# 6_CLOCK.net
KiCad netlist of a schematic drawn in Altium Designer
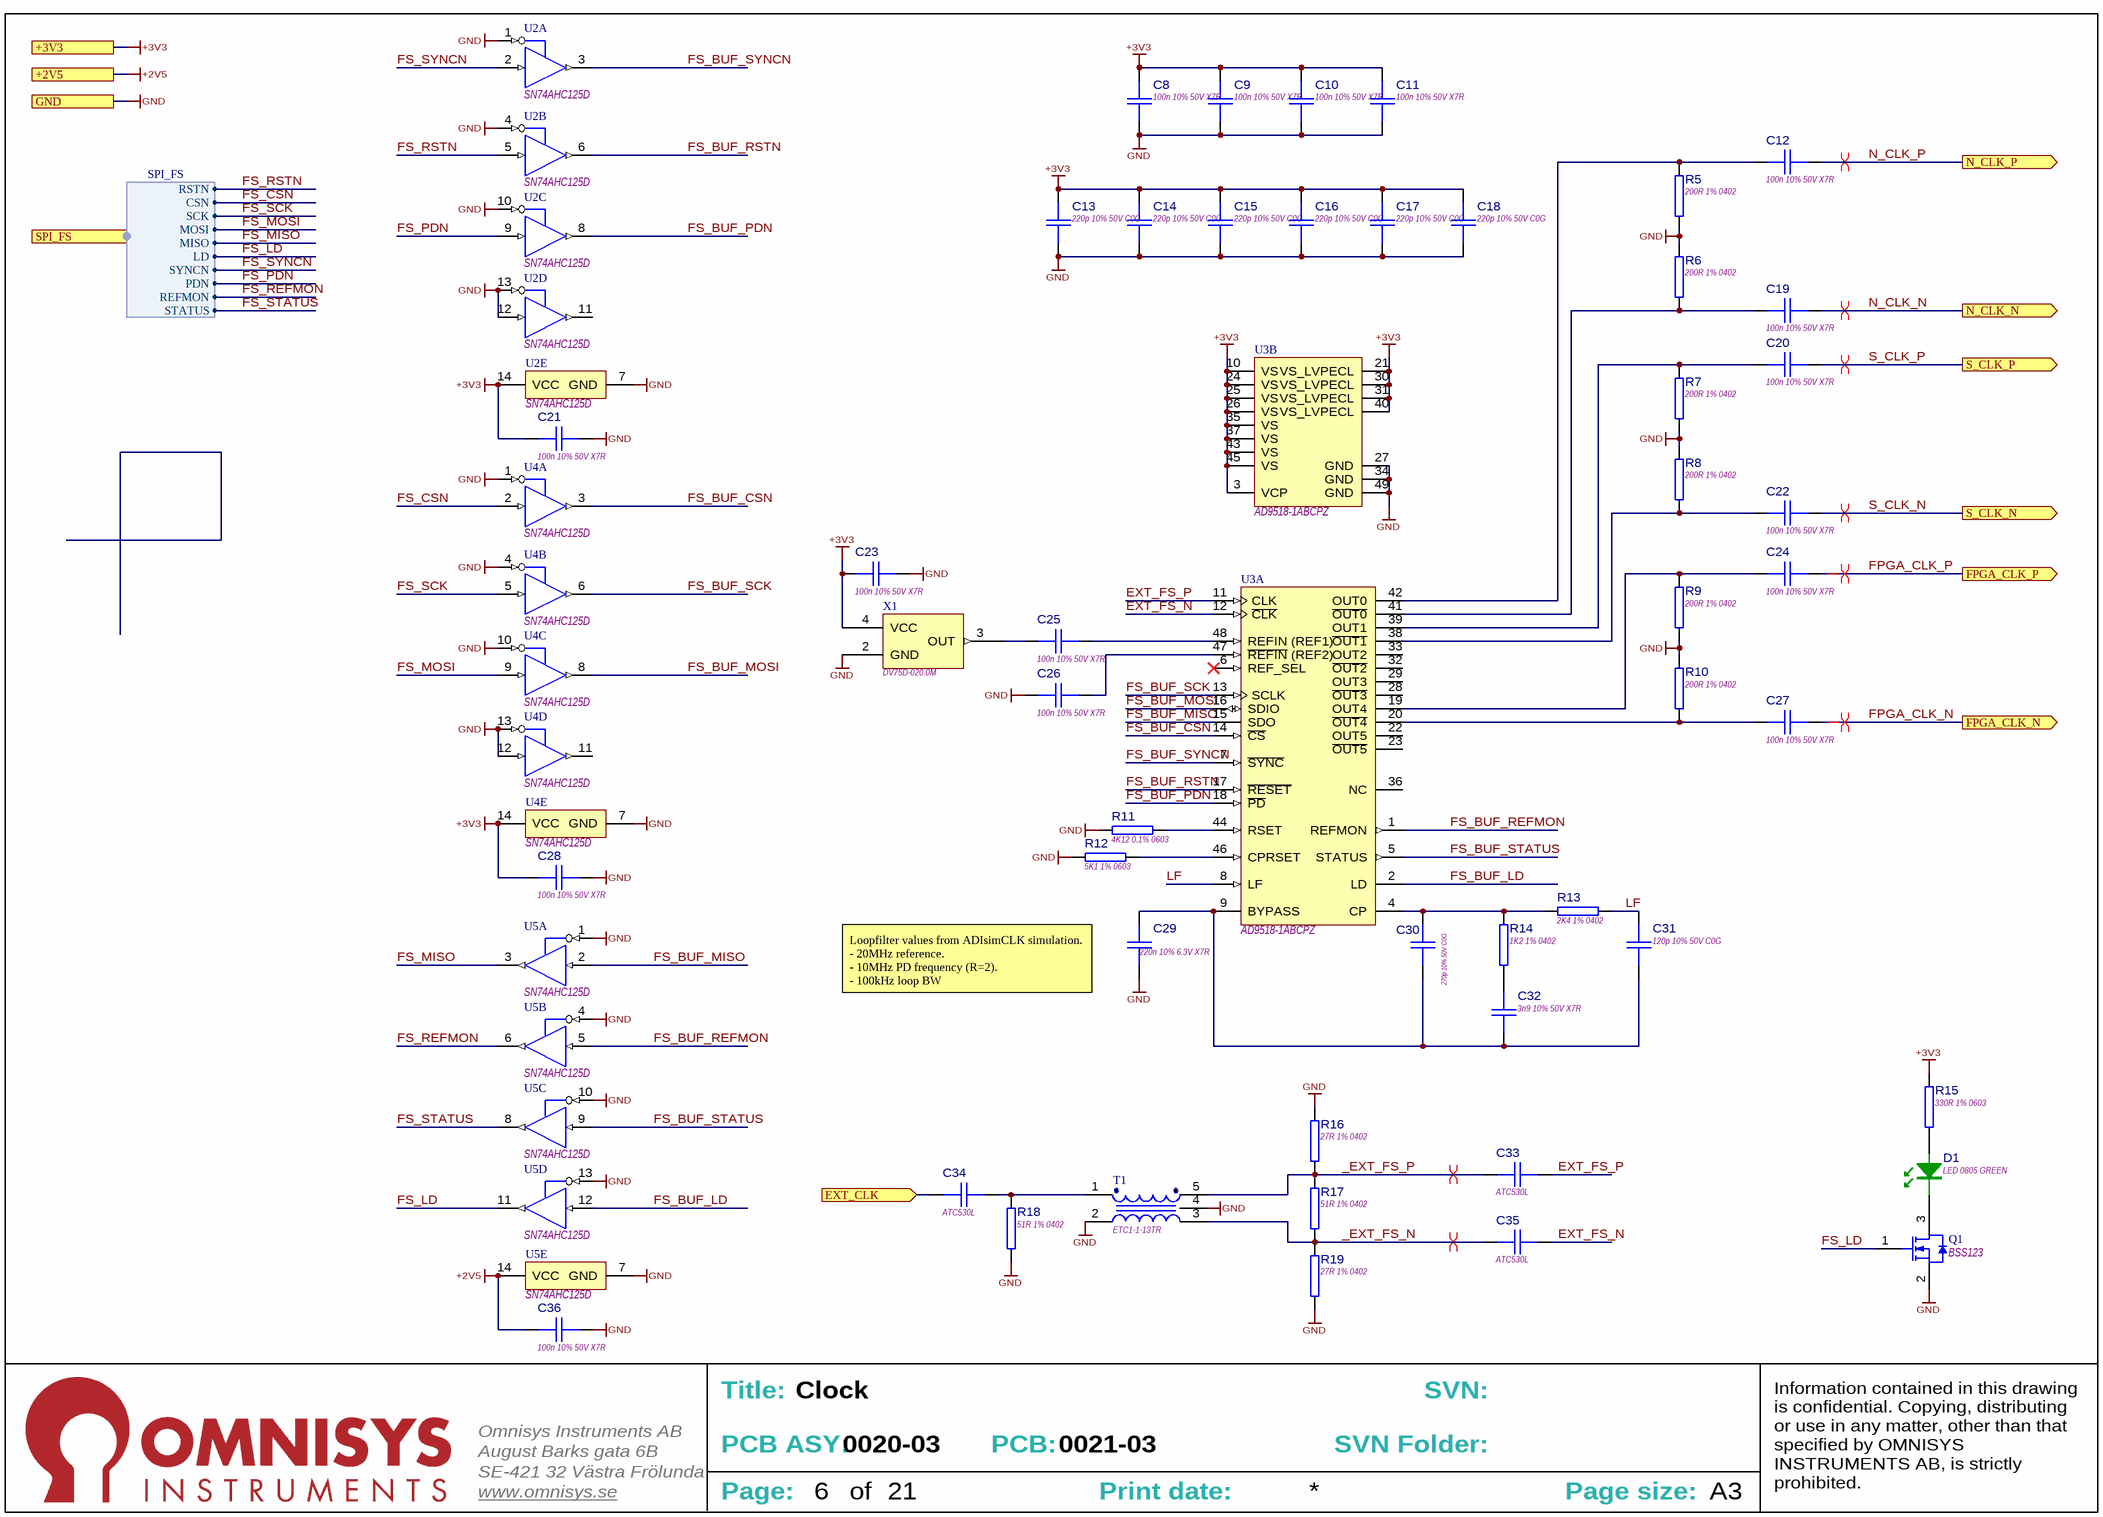
[diagram p0: [6] CLOCK.SchDoc]

(export (version "E")
  (design (tool "Eeschema 10.0.6"))
  (components
    (comp (ref "C8")
      (value "100n 10% 50V X7R")
      (footprint "CAPC1608X90N")
      (description "Ceramic Chip Capacitor, 0603/1608")
      (fields (field (name "TOLERANCE") "10%"))
      (libsource (lib "Omnisys Vault") (part "CAP-2PIN"))
    )
    (comp (ref "C9")
      (value "100n 10% 50V X7R")
      (footprint "CAPC1608X90N")
      (description "Ceramic Chip Capacitor, 0603/1608")
      (fields (field (name "TOLERANCE") "10%"))
      (libsource (lib "Omnisys Vault") (part "CAP-2PIN"))
    )
    (comp (ref "C10")
      (value "100n 10% 50V X7R")
      (footprint "CAPC1608X90N")
      (description "Ceramic Chip Capacitor, 0603/1608")
      (fields (field (name "TOLERANCE") "10%"))
      (libsource (lib "Omnisys Vault") (part "CAP-2PIN"))
    )
    (comp (ref "C11")
      (value "100n 10% 50V X7R")
      (footprint "CAPC1608X90N")
      (description "Ceramic Chip Capacitor, 0603/1608")
      (fields (field (name "TOLERANCE") "10%"))
      (libsource (lib "Omnisys Vault") (part "CAP-2PIN"))
    )
    (comp (ref "C12")
      (value "100n 10% 50V X7R")
      (footprint "CAPC1005X55L")
      (description "Ceramic Chip Capacitor, 0402/1005")
      (fields (field (name "TOLERANCE") "10%"))
      (libsource (lib "Omnisys Vault") (part "CAP-2PIN"))
    )
    (comp (ref "C13")
      (value "220p 10% 50V C0G")
      (footprint "CAPC1005X55N")
      (description "Ceramic Chip Capacitor, 0402/1005")
      (fields (field (name "TOLERANCE") "10%"))
      (libsource (lib "Omnisys Vault") (part "CAP-2PIN"))
    )
    (comp (ref "C14")
      (value "220p 10% 50V C0G")
      (footprint "CAPC1005X55N")
      (description "Ceramic Chip Capacitor, 0402/1005")
      (fields (field (name "TOLERANCE") "10%"))
      (libsource (lib "Omnisys Vault") (part "CAP-2PIN"))
    )
    (comp (ref "C15")
      (value "220p 10% 50V C0G")
      (footprint "CAPC1005X55N")
      (description "Ceramic Chip Capacitor, 0402/1005")
      (fields (field (name "TOLERANCE") "10%"))
      (libsource (lib "Omnisys Vault") (part "CAP-2PIN"))
    )
    (comp (ref "C16")
      (value "220p 10% 50V C0G")
      (footprint "CAPC1005X55N")
      (description "Ceramic Chip Capacitor, 0402/1005")
      (fields (field (name "TOLERANCE") "10%"))
      (libsource (lib "Omnisys Vault") (part "CAP-2PIN"))
    )
    (comp (ref "C17")
      (value "220p 10% 50V C0G")
      (footprint "CAPC1005X55N")
      (description "Ceramic Chip Capacitor, 0402/1005")
      (fields (field (name "TOLERANCE") "10%"))
      (libsource (lib "Omnisys Vault") (part "CAP-2PIN"))
    )
    (comp (ref "C18")
      (value "220p 10% 50V C0G")
      (footprint "CAPC1005X55N")
      (description "Ceramic Chip Capacitor, 0402/1005")
      (fields (field (name "TOLERANCE") "10%"))
      (libsource (lib "Omnisys Vault") (part "CAP-2PIN"))
    )
    (comp (ref "C19")
      (value "100n 10% 50V X7R")
      (footprint "CAPC1005X55L")
      (description "Ceramic Chip Capacitor, 0402/1005")
      (fields (field (name "TOLERANCE") "10%"))
      (libsource (lib "Omnisys Vault") (part "CAP-2PIN"))
    )
    (comp (ref "C20")
      (value "100n 10% 50V X7R")
      (footprint "CAPC1005X55L")
      (description "Ceramic Chip Capacitor, 0402/1005")
      (fields (field (name "TOLERANCE") "10%"))
      (libsource (lib "Omnisys Vault") (part "CAP-2PIN"))
    )
    (comp (ref "C21")
      (value "100n 10% 50V X7R")
      (footprint "CAPC1608X90N")
      (description "Ceramic Chip Capacitor, 0603/1608")
      (fields (field (name "TOLERANCE") "10%"))
      (libsource (lib "Omnisys Vault") (part "CAP-2PIN"))
    )
    (comp (ref "C22")
      (value "100n 10% 50V X7R")
      (footprint "CAPC1005X55L")
      (description "Ceramic Chip Capacitor, 0402/1005")
      (fields (field (name "TOLERANCE") "10%"))
      (libsource (lib "Omnisys Vault") (part "CAP-2PIN"))
    )
    (comp (ref "C23")
      (value "100n 10% 50V X7R")
      (footprint "CAPC1608X90N")
      (description "Ceramic Chip Capacitor, 0603/1608")
      (fields (field (name "TOLERANCE") "10%"))
      (libsource (lib "Omnisys Vault") (part "CAP-2PIN"))
    )
    (comp (ref "C24")
      (value "100n 10% 50V X7R")
      (footprint "CAPC1005X55L")
      (description "Ceramic Chip Capacitor, 0402/1005")
      (fields (field (name "TOLERANCE") "10%"))
      (libsource (lib "Omnisys Vault") (part "CAP-2PIN"))
    )
    (comp (ref "C25")
      (value "100n 10% 50V X7R")
      (footprint "CAPC1005X55L")
      (description "Ceramic Chip Capacitor, 0402/1005")
      (fields (field (name "TOLERANCE") "10%"))
      (libsource (lib "Omnisys Vault") (part "CAP-2PIN"))
    )
    (comp (ref "C26")
      (value "100n 10% 50V X7R")
      (footprint "CAPC1005X55L")
      (description "Ceramic Chip Capacitor, 0402/1005")
      (fields (field (name "TOLERANCE") "10%"))
      (libsource (lib "Omnisys Vault") (part "CAP-2PIN"))
    )
    (comp (ref "C27")
      (value "100n 10% 50V X7R")
      (footprint "CAPC1005X55L")
      (description "Ceramic Chip Capacitor, 0402/1005")
      (fields (field (name "TOLERANCE") "10%"))
      (libsource (lib "Omnisys Vault") (part "CAP-2PIN"))
    )
    (comp (ref "C28")
      (value "100n 10% 50V X7R")
      (footprint "CAPC1608X90N")
      (description "Ceramic Chip Capacitor, 0603/1608")
      (fields (field (name "TOLERANCE") "10%"))
      (libsource (lib "Omnisys Vault") (part "CAP-2PIN"))
    )
    (comp (ref "C29")
      (value "220n 10% 6.3V X7R")
      (footprint "CAPC1608X90L")
      (description "Ceramic Chip Capacitor, 0603/1608")
      (fields (field (name "TOLERANCE") "10%"))
      (libsource (lib "Omnisys Vault") (part "CAP-2PIN"))
    )
    (comp (ref "C30")
      (value "270p 10% 50V C0G")
      (footprint "CAPC1005X55L")
      (description "Ceramic Chip Capacitor, 0402/1005")
      (fields (field (name "TOLERANCE") "10%"))
      (libsource (lib "Omnisys Vault") (part "CAP-2PIN"))
    )
    (comp (ref "C31")
      (value "120p 10% 50V C0G")
      (footprint "CAPC1005X55L")
      (description "Ceramic Chip Capacitor, 0402/1005")
      (fields (field (name "TOLERANCE") "10%"))
      (libsource (lib "Omnisys Vault") (part "CAP-2PIN"))
    )
    (comp (ref "C32")
      (value "3n9 10% 50V X7R")
      (footprint "CAPC1005X55L")
      (description "Ceramic Chip Capacitor, 0402/1005")
      (fields (field (name "TOLERANCE") "10%"))
      (libsource (lib "Omnisys Vault") (part "CAP-2PIN"))
    )
    (comp (ref "C33")
      (value "ATC530L")
      (footprint "CAPC1005X06L")
      (description "100n 16V ±15% 0402 (1005 metric) ATC530L104KT16T")
      (fields (field (name "TOLERANCE") "±15%"))
      (libsource (lib "Omnisys Vault") (part "CAP-2PIN"))
    )
    (comp (ref "C34")
      (value "ATC530L")
      (footprint "CAPC1005X06L")
      (description "100n 16V ±15% 0402 (1005 metric) ATC530L104KT16T")
      (fields (field (name "TOLERANCE") "±15%"))
      (libsource (lib "Omnisys Vault") (part "CAP-2PIN"))
    )
    (comp (ref "C35")
      (value "ATC530L")
      (footprint "CAPC1005X06L")
      (description "100n 16V ±15% 0402 (1005 metric) ATC530L104KT16T")
      (fields (field (name "TOLERANCE") "±15%"))
      (libsource (lib "Omnisys Vault") (part "CAP-2PIN"))
    )
    (comp (ref "C36")
      (value "100n 10% 50V X7R")
      (footprint "CAPC1608X90N")
      (description "Ceramic Chip Capacitor, 0603/1608")
      (fields (field (name "TOLERANCE") "10%"))
      (libsource (lib "Omnisys Vault") (part "CAP-2PIN"))
    )
    (comp (ref "D1")
      (value "LED 0805 GREEN")
      (footprint "LED2012-GREEN")
      (libsource (lib "Omnisys Vault") (part "LED-2PIN-GREEN"))
    )
    (comp (ref "Q1")
      (value "BSS123")
      (footprint "SOT95P230X110-3N")
      (description "MOSFET N-CH 100V 170MA SOT-23")
      (fields (field (name "VOLTAGE") "100V"))
      (libsource (lib "Omnisys Vault") (part "NEMOS-GSD-3"))
    )
    (comp (ref "R5")
      (value "200R 1% 0402")
      (footprint "RESC1005L")
      (description "Thick film Chip Resistor, 0402/1005")
      (fields (field (name "POWER") "100mW") (field (name "TOLERANCE") "1%"))
      (libsource (lib "Omnisys Vault") (part "RES-2PIN"))
    )
    (comp (ref "R6")
      (value "200R 1% 0402")
      (footprint "RESC1005L")
      (description "Thick film Chip Resistor, 0402/1005")
      (fields (field (name "POWER") "100mW") (field (name "TOLERANCE") "1%"))
      (libsource (lib "Omnisys Vault") (part "RES-2PIN"))
    )
    (comp (ref "R7")
      (value "200R 1% 0402")
      (footprint "RESC1005L")
      (description "Thick film Chip Resistor, 0402/1005")
      (fields (field (name "POWER") "100mW") (field (name "TOLERANCE") "1%"))
      (libsource (lib "Omnisys Vault") (part "RES-2PIN"))
    )
    (comp (ref "R8")
      (value "200R 1% 0402")
      (footprint "RESC1005L")
      (description "Thick film Chip Resistor, 0402/1005")
      (fields (field (name "POWER") "100mW") (field (name "TOLERANCE") "1%"))
      (libsource (lib "Omnisys Vault") (part "RES-2PIN"))
    )
    (comp (ref "R9")
      (value "200R 1% 0402")
      (footprint "RESC1005L")
      (description "Thick film Chip Resistor, 0402/1005")
      (fields (field (name "POWER") "100mW") (field (name "TOLERANCE") "1%"))
      (libsource (lib "Omnisys Vault") (part "RES-2PIN"))
    )
    (comp (ref "R10")
      (value "200R 1% 0402")
      (footprint "RESC1005L")
      (description "Thick film Chip Resistor, 0402/1005")
      (fields (field (name "POWER") "100mW") (field (name "TOLERANCE") "1%"))
      (libsource (lib "Omnisys Vault") (part "RES-2PIN"))
    )
    (comp (ref "R11")
      (value "4K12 0.1% 0603")
      (footprint "RESC1608N")
      (description "Thin film Chip Resistor, 0603/1608")
      (fields (field (name "POWER") "100mW") (field (name "TOLERANCE") "0.1%"))
      (libsource (lib "Omnisys Vault") (part "RES-2PIN"))
    )
    (comp (ref "R12")
      (value "5K1 1% 0603")
      (footprint "RESC1608N")
      (description "Thick film Chip Resistor, 0603/1608")
      (fields (field (name "POWER") "100mW") (field (name "TOLERANCE") "1%"))
      (libsource (lib "Omnisys Vault") (part "RES-2PIN"))
    )
    (comp (ref "R13")
      (value "2K4 1% 0402")
      (footprint "RESC1005L")
      (description "Thick film Chip Resistor, 0402/1005")
      (fields (field (name "POWER") "100mW") (field (name "TOLERANCE") "1%"))
      (libsource (lib "Omnisys Vault") (part "RES-2PIN"))
    )
    (comp (ref "R14")
      (value "1K2 1% 0402")
      (footprint "RESC1005L")
      (description "Thick film Chip Resistor, 0402/1005")
      (fields (field (name "POWER") "100mW") (field (name "TOLERANCE") "1%"))
      (libsource (lib "Omnisys Vault") (part "RES-2PIN"))
    )
    (comp (ref "R15")
      (value "330R 1% 0603")
      (footprint "RESC1608N")
      (description "Thick film Chip Resistor, 0603/1608")
      (fields (field (name "POWER") "100mW") (field (name "TOLERANCE") "1%"))
      (libsource (lib "Omnisys Vault") (part "RES-2PIN"))
    )
    (comp (ref "R16")
      (value "27R 1% 0402")
      (footprint "RESC1005L")
      (description "Thick film Chip Resistor, 0402/1005")
      (fields (field (name "POWER") "100mW") (field (name "TOLERANCE") "1%"))
      (libsource (lib "Omnisys Vault") (part "RES-2PIN"))
    )
    (comp (ref "R17")
      (value "51R 1% 0402")
      (footprint "RESC1005L")
      (description "Thick film Chip Resistor, 0402/1005")
      (fields (field (name "POWER") "100mW") (field (name "TOLERANCE") "1%"))
      (libsource (lib "Omnisys Vault") (part "RES-2PIN"))
    )
    (comp (ref "R18")
      (value "51R 1% 0402")
      (footprint "RESC1005L")
      (description "Thick film Chip Resistor, 0402/1005")
      (fields (field (name "POWER") "100mW") (field (name "TOLERANCE") "1%"))
      (libsource (lib "Omnisys Vault") (part "RES-2PIN"))
    )
    (comp (ref "R19")
      (value "27R 1% 0402")
      (footprint "RESC1005L")
      (description "Thick film Chip Resistor, 0402/1005")
      (fields (field (name "POWER") "100mW") (field (name "TOLERANCE") "1%"))
      (libsource (lib "Omnisys Vault") (part "RES-2PIN"))
    )
    (comp (ref "T1")
      (value "ETC1-1-13TR")
      (footprint "SOTFL50P160X73-3N")
      (description "Transformers Audio & Signal 4.5-3000MHz IL 2dB Impedance Ratio 1:1")
      (libsource (lib "Omnisys Vault") (part "ETC1-1-13TR"))
    )
    (comp (ref "U2")
      (value "SN74AHC125D")
      (footprint "SOIC127P600X175-14N")
      (description "Buffer/Line Driver 4-CH Non-Inverting 3-ST CMOS 14-Pin SOIC Tube")
      (libsource (lib "Omnisys Vault") (part "SN74AHC125D"))
    )
    (comp (ref "U3")
      (value "AD9518-1ABCPZ")
      (footprint "ADI-CP-48-8_M")
      (description "IC CLOCK GEN 6CH 2.65GHZ 48LFCSP")
      (libsource (lib "Omnisys Vault") (part "ADI-AD9518-1-CP-48-8"))
    )
    (comp (ref "U4")
      (value "SN74AHC125D")
      (footprint "SOIC127P600X175-14N")
      (description "Buffer/Line Driver 4-CH Non-Inverting 3-ST CMOS 14-Pin SOIC Tube")
      (libsource (lib "Omnisys Vault") (part "SN74AHC125D"))
    )
    (comp (ref "U5")
      (value "SN74AHC125D")
      (footprint "SOIC127P600X175-14N")
      (description "Buffer/Line Driver 4-CH Non-Inverting 3-ST CMOS 14-Pin SOIC Tube")
      (libsource (lib "") (part "SN74AHC125D_1"))
    )
    (comp (ref "X1")
      (value "DV75D-020.0M")
      (footprint "DV75D")
      (description "OSC TCXO 20.000MHZ LVCMOS SMD")
      (libsource (lib "Omnisys Vault") (part "DV75D-020.0M"))
    )
  )
  (nets
    (net (code "2") (name "+2V5") (class "Default")
      (node (ref "C36") (pin "2") (pinfunction "2_2") (pintype "passive"))
      (node (ref "U5") (pin "14") (pinfunction "VCC_14") (pintype "power_in"))
    )
    (net (code "3") (name "+3V3") (class "Default")
      (node (ref "C10") (pin "2") (pinfunction "2_2") (pintype "passive"))
      (node (ref "C11") (pin "2") (pinfunction "2_2") (pintype "passive"))
      (node (ref "C13") (pin "2") (pinfunction "2_2") (pintype "passive"))
      (node (ref "C14") (pin "2") (pinfunction "2_2") (pintype "passive"))
      (node (ref "C15") (pin "2") (pinfunction "2_2") (pintype "passive"))
      (node (ref "C16") (pin "2") (pinfunction "2_2") (pintype "passive"))
      (node (ref "C17") (pin "2") (pinfunction "2_2") (pintype "passive"))
      (node (ref "C18") (pin "2") (pinfunction "2_2") (pintype "passive"))
      (node (ref "C21") (pin "2") (pinfunction "2_2") (pintype "passive"))
      (node (ref "C23") (pin "2") (pinfunction "2_2") (pintype "passive"))
      (node (ref "C28") (pin "2") (pinfunction "2_2") (pintype "passive"))
      (node (ref "C8") (pin "2") (pinfunction "2_2") (pintype "passive"))
      (node (ref "C9") (pin "2") (pinfunction "2_2") (pintype "passive"))
      (node (ref "R15") (pin "2") (pinfunction "2_2") (pintype "passive"))
      (node (ref "U2") (pin "14") (pinfunction "VCC_14") (pintype "power_in"))
      (node (ref "U3") (pin "10") (pinfunction "VS_10") (pintype "power_in"))
      (node (ref "U3") (pin "21") (pinfunction "VS_LVPECL_21") (pintype "power_in"))
      (node (ref "U3") (pin "24") (pinfunction "VS_24") (pintype "power_in"))
      (node (ref "U3") (pin "25") (pinfunction "VS_25") (pintype "power_in"))
      (node (ref "U3") (pin "26") (pinfunction "VS_26") (pintype "power_in"))
      (node (ref "U3") (pin "3") (pinfunction "VCP_3") (pintype "power_in"))
      (node (ref "U3") (pin "30") (pinfunction "VS_LVPECL_30") (pintype "power_in"))
      (node (ref "U3") (pin "31") (pinfunction "VS_LVPECL_31") (pintype "power_in"))
      (node (ref "U3") (pin "35") (pinfunction "VS_35") (pintype "power_in"))
      (node (ref "U3") (pin "37") (pinfunction "VS_37") (pintype "power_in"))
      (node (ref "U3") (pin "40") (pinfunction "VS_LVPECL_40") (pintype "power_in"))
      (node (ref "U3") (pin "43") (pinfunction "VS_43") (pintype "power_in"))
      (node (ref "U3") (pin "45") (pinfunction "VS_45") (pintype "power_in"))
      (node (ref "U4") (pin "14") (pinfunction "VCC_14") (pintype "power_in"))
      (node (ref "X1") (pin "4") (pinfunction "VCC_4") (pintype "power_in"))
    )
    (net (code "4") (name "/EXT_CLK") (class "Default")
      (node (ref "C34") (pin "1") (pinfunction "1_1") (pintype "passive"))
    )
    (net (code "5") (name "/EXT_FS_N") (class "Default")
      (node (ref "C35") (pin "2") (pinfunction "2_2") (pintype "passive"))
      (node (ref "U3") (pin "12") (pinfunction "~{CLK}_12") (pintype "input"))
    )
    (net (code "6") (name "/EXT_FS_P") (class "Default")
      (node (ref "C33") (pin "2") (pinfunction "2_2") (pintype "passive"))
      (node (ref "U3") (pin "11") (pinfunction "CLK_11") (pintype "input"))
    )
    (net (code "7") (name "/FPGA_CLK_N") (class "Default")
      (node (ref "C27") (pin "1") (pinfunction "1_1") (pintype "passive"))
    )
    (net (code "8") (name "/FPGA_CLK_P") (class "Default")
      (node (ref "C24") (pin "1") (pinfunction "1_1") (pintype "passive"))
    )
    (net (code "9") (name "/FS_BUF_CSN") (class "Default")
      (node (ref "U3") (pin "14") (pinfunction "~{CS}_14") (pintype "input"))
      (node (ref "U4") (pin "3") (pinfunction "1Y_3") (pintype "output"))
    )
    (net (code "10") (name "/FS_BUF_LD") (class "Default")
      (node (ref "U3") (pin "2") (pinfunction "LD_2") (pintype "tri_state"))
      (node (ref "U5") (pin "12") (pinfunction "4A_12") (pintype "input"))
    )
    (net (code "11") (name "/FS_BUF_MISO") (class "Default")
      (node (ref "U3") (pin "15") (pinfunction "SDO_15") (pintype "tri_state"))
      (node (ref "U5") (pin "2") (pinfunction "1A_2") (pintype "input"))
    )
    (net (code "12") (name "/FS_BUF_MOSI") (class "Default")
      (node (ref "U3") (pin "16") (pinfunction "SDIO_16") (pintype "bidirectional"))
      (node (ref "U4") (pin "8") (pinfunction "3Y_8") (pintype "output"))
    )
    (net (code "13") (name "/FS_BUF_PDN") (class "Default")
      (node (ref "U2") (pin "8") (pinfunction "3Y_8") (pintype "output"))
      (node (ref "U3") (pin "18") (pinfunction "~{PD}_18") (pintype "input"))
    )
    (net (code "14") (name "/FS_BUF_REFMON") (class "Default")
      (node (ref "U3") (pin "1") (pinfunction "REFMON_1") (pintype "output"))
      (node (ref "U5") (pin "5") (pinfunction "2A_5") (pintype "input"))
    )
    (net (code "15") (name "/FS_BUF_RSTN") (class "Default")
      (node (ref "U2") (pin "6") (pinfunction "2Y_6") (pintype "output"))
      (node (ref "U3") (pin "17") (pinfunction "~{RESET}_17") (pintype "input"))
    )
    (net (code "16") (name "/FS_BUF_SCK") (class "Default")
      (node (ref "U3") (pin "13") (pinfunction "SCLK_13") (pintype "input"))
      (node (ref "U4") (pin "6") (pinfunction "2Y_6") (pintype "output"))
    )
    (net (code "17") (name "/FS_BUF_STATUS") (class "Default")
      (node (ref "U3") (pin "5") (pinfunction "STATUS_5") (pintype "output"))
      (node (ref "U5") (pin "9") (pinfunction "3A_9") (pintype "input"))
    )
    (net (code "18") (name "/FS_BUF_SYNCN") (class "Default")
      (node (ref "U2") (pin "3") (pinfunction "1Y_3") (pintype "output"))
      (node (ref "U3") (pin "7") (pinfunction "~{SYNC}_7") (pintype "input"))
    )
    (net (code "19") (name "/FS_CSN") (class "Default")
      (node (ref "U4") (pin "2") (pinfunction "1A_2") (pintype "input"))
    )
    (net (code "20") (name "/FS_LD") (class "Default")
      (node (ref "Q1") (pin "1") (pinfunction "G_1") (pintype "passive"))
      (node (ref "U5") (pin "11") (pinfunction "4Y_11") (pintype "output"))
    )
    (net (code "21") (name "/FS_MISO") (class "Default")
      (node (ref "U5") (pin "3") (pinfunction "1Y_3") (pintype "output"))
    )
    (net (code "22") (name "/FS_MOSI") (class "Default")
      (node (ref "U4") (pin "9") (pinfunction "3A_9") (pintype "input"))
    )
    (net (code "23") (name "/FS_PDN") (class "Default")
      (node (ref "U2") (pin "9") (pinfunction "3A_9") (pintype "input"))
    )
    (net (code "24") (name "/FS_REFMON") (class "Default")
      (node (ref "U5") (pin "6") (pinfunction "2Y_6") (pintype "output"))
    )
    (net (code "25") (name "/FS_RSTN") (class "Default")
      (node (ref "U2") (pin "5") (pinfunction "2A_5") (pintype "input"))
    )
    (net (code "26") (name "/FS_SCK") (class "Default")
      (node (ref "U4") (pin "5") (pinfunction "2A_5") (pintype "input"))
    )
    (net (code "27") (name "/FS_STATUS") (class "Default")
      (node (ref "U5") (pin "8") (pinfunction "3Y_8") (pintype "output"))
    )
    (net (code "28") (name "/FS_SYNCN") (class "Default")
      (node (ref "U2") (pin "2") (pinfunction "1A_2") (pintype "input"))
    )
    (net (code "29") (name "/LF") (class "Default")
      (node (ref "C31") (pin "2") (pinfunction "2_2") (pintype "passive"))
      (node (ref "R13") (pin "2") (pinfunction "2_2") (pintype "passive"))
      (node (ref "U3") (pin "8") (pinfunction "LF_8") (pintype "input"))
    )
    (net (code "30") (name "/N_CLK_N") (class "Default")
      (node (ref "C19") (pin "1") (pinfunction "1_1") (pintype "passive"))
    )
    (net (code "31") (name "/N_CLK_P") (class "Default")
      (node (ref "C12") (pin "1") (pinfunction "1_1") (pintype "passive"))
    )
    (net (code "32") (name "/S_CLK_N") (class "Default")
      (node (ref "C22") (pin "1") (pinfunction "1_1") (pintype "passive"))
    )
    (net (code "33") (name "/S_CLK_P") (class "Default")
      (node (ref "C20") (pin "1") (pinfunction "1_1") (pintype "passive"))
    )
    (net (code "34") (name "/_EXT_FS_N") (class "Default")
      (node (ref "C35") (pin "1") (pinfunction "1_1") (pintype "passive"))
      (node (ref "R17") (pin "1") (pinfunction "1_1") (pintype "passive"))
      (node (ref "R19") (pin "1") (pinfunction "1_1") (pintype "passive"))
      (node (ref "T1") (pin "3") (pinfunction "Secondary_3") (pintype "passive"))
    )
    (net (code "35") (name "/_EXT_FS_P") (class "Default")
      (node (ref "C33") (pin "1") (pinfunction "1_1") (pintype "passive"))
      (node (ref "R16") (pin "1") (pinfunction "1_1") (pintype "passive"))
      (node (ref "R17") (pin "2") (pinfunction "2_2") (pintype "passive"))
      (node (ref "T1") (pin "5") (pinfunction "Secondary_dot_5") (pintype "passive"))
    )
    (net (code "37") (name "GND") (class "Default")
      (node (ref "C10") (pin "1") (pinfunction "1_1") (pintype "passive"))
      (node (ref "C11") (pin "1") (pinfunction "1_1") (pintype "passive"))
      (node (ref "C13") (pin "1") (pinfunction "1_1") (pintype "passive"))
      (node (ref "C14") (pin "1") (pinfunction "1_1") (pintype "passive"))
      (node (ref "C15") (pin "1") (pinfunction "1_1") (pintype "passive"))
      (node (ref "C16") (pin "1") (pinfunction "1_1") (pintype "passive"))
      (node (ref "C17") (pin "1") (pinfunction "1_1") (pintype "passive"))
      (node (ref "C18") (pin "1") (pinfunction "1_1") (pintype "passive"))
      (node (ref "C21") (pin "1") (pinfunction "1_1") (pintype "passive"))
      (node (ref "C23") (pin "1") (pinfunction "1_1") (pintype "passive"))
      (node (ref "C26") (pin "2") (pinfunction "2_2") (pintype "passive"))
      (node (ref "C28") (pin "1") (pinfunction "1_1") (pintype "passive"))
      (node (ref "C29") (pin "2") (pinfunction "2_2") (pintype "passive"))
      (node (ref "C36") (pin "1") (pinfunction "1_1") (pintype "passive"))
      (node (ref "C8") (pin "1") (pinfunction "1_1") (pintype "passive"))
      (node (ref "C9") (pin "1") (pinfunction "1_1") (pintype "passive"))
      (node (ref "Q1") (pin "2") (pinfunction "S_2") (pintype "passive"))
      (node (ref "R10") (pin "2") (pinfunction "2_2") (pintype "passive"))
      (node (ref "R11") (pin "1") (pinfunction "1_1") (pintype "passive"))
      (node (ref "R12") (pin "1") (pinfunction "1_1") (pintype "passive"))
      (node (ref "R16") (pin "2") (pinfunction "2_2") (pintype "passive"))
      (node (ref "R18") (pin "2") (pinfunction "2_2") (pintype "passive"))
      (node (ref "R19") (pin "2") (pinfunction "2_2") (pintype "passive"))
      (node (ref "R5") (pin "2") (pinfunction "2_2") (pintype "passive"))
      (node (ref "R6") (pin "2") (pinfunction "2_2") (pintype "passive"))
      (node (ref "R7") (pin "2") (pinfunction "2_2") (pintype "passive"))
      (node (ref "R8") (pin "2") (pinfunction "2_2") (pintype "passive"))
      (node (ref "R9") (pin "2") (pinfunction "2_2") (pintype "passive"))
      (node (ref "T1") (pin "2") (pinfunction "Primary_2") (pintype "passive"))
      (node (ref "T1") (pin "4") (pinfunction "NC_4") (pintype "passive"))
      (node (ref "U2") (pin "1") (pinfunction "1OE#_1") (pintype "input"))
      (node (ref "U2") (pin "10") (pinfunction "3OE#_10") (pintype "input"))
      (node (ref "U2") (pin "12") (pinfunction "4A_12") (pintype "input"))
      (node (ref "U2") (pin "13") (pinfunction "4OE#_13") (pintype "input"))
      (node (ref "U2") (pin "4") (pinfunction "2OE#_4") (pintype "input"))
      (node (ref "U2") (pin "7") (pinfunction "GND_7") (pintype "power_in"))
      (node (ref "U3") (pin "27") (pinfunction "GND_27") (pintype "power_in"))
      (node (ref "U3") (pin "34") (pinfunction "GND_34") (pintype "power_in"))
      (node (ref "U3") (pin "49") (pinfunction "GND_49") (pintype "power_in"))
      (node (ref "U4") (pin "1") (pinfunction "1OE#_1") (pintype "input"))
      (node (ref "U4") (pin "10") (pinfunction "3OE#_10") (pintype "input"))
      (node (ref "U4") (pin "12") (pinfunction "4A_12") (pintype "input"))
      (node (ref "U4") (pin "13") (pinfunction "4OE#_13") (pintype "input"))
      (node (ref "U4") (pin "4") (pinfunction "2OE#_4") (pintype "input"))
      (node (ref "U4") (pin "7") (pinfunction "GND_7") (pintype "power_in"))
      (node (ref "U5") (pin "1") (pinfunction "1OE#_1") (pintype "input"))
      (node (ref "U5") (pin "10") (pinfunction "3OE#_10") (pintype "input"))
      (node (ref "U5") (pin "13") (pinfunction "4OE#_13") (pintype "input"))
      (node (ref "U5") (pin "4") (pinfunction "2OE#_4") (pintype "input"))
      (node (ref "U5") (pin "7") (pinfunction "GND_7") (pintype "power_in"))
      (node (ref "X1") (pin "2") (pinfunction "GND_2") (pintype "power_in"))
    )
    (net (code "38") (name "Net-(C32-Pad1)") (class "Default")
      (node (ref "C32") (pin "1") (pinfunction "1_1") (pintype "passive"))
      (node (ref "R14") (pin "1") (pinfunction "1_1") (pintype "passive"))
    )
    (net (code "39") (name "Net-(D1-Pad2)") (class "Default")
      (node (ref "D1") (pin "2") (pintype "passive"))
      (node (ref "R15") (pin "1") (pinfunction "1_1") (pintype "passive"))
    )
    (net (code "40") (name "Net-(Q1-D)") (class "Default")
      (node (ref "D1") (pin "1") (pintype "passive"))
      (node (ref "Q1") (pin "3") (pinfunction "D_3") (pintype "passive"))
    )
    (net (code "41") (name "Net-(T1-Primary_dot)") (class "Default")
      (node (ref "C34") (pin "2") (pinfunction "2_2") (pintype "passive"))
      (node (ref "R18") (pin "1") (pinfunction "1_1") (pintype "passive"))
      (node (ref "T1") (pin "1") (pinfunction "Primary_dot_1") (pintype "passive"))
    )
    (net (code "42") (name "Net-(U3A-BYPASS)") (class "Default")
      (node (ref "C29") (pin "1") (pinfunction "1_1") (pintype "passive"))
      (node (ref "C30") (pin "2") (pinfunction "2_2") (pintype "passive"))
      (node (ref "C31") (pin "1") (pinfunction "1_1") (pintype "passive"))
      (node (ref "C32") (pin "2") (pinfunction "2_2") (pintype "passive"))
      (node (ref "U3") (pin "9") (pinfunction "BYPASS_9") (pintype "passive"))
    )
    (net (code "43") (name "Net-(U3A-CP)") (class "Default")
      (node (ref "C30") (pin "1") (pinfunction "1_1") (pintype "passive"))
      (node (ref "R13") (pin "1") (pinfunction "1_1") (pintype "passive"))
      (node (ref "R14") (pin "2") (pinfunction "2_2") (pintype "passive"))
      (node (ref "U3") (pin "4") (pinfunction "CP_4") (pintype "tri_state"))
    )
    (net (code "44") (name "Net-(U3A-CPRSET)") (class "Default")
      (node (ref "R12") (pin "2") (pinfunction "2_2") (pintype "passive"))
      (node (ref "U3") (pin "46") (pinfunction "CPRSET_46") (pintype "input"))
    )
    (net (code "45") (name "Net-(U3A-OUT0)") (class "Default")
      (node (ref "C12") (pin "2") (pinfunction "2_2") (pintype "passive"))
      (node (ref "R5") (pin "1") (pinfunction "1_1") (pintype "passive"))
      (node (ref "U3") (pin "42") (pinfunction "OUT0_42") (pintype "tri_state"))
    )
    (net (code "46") (name "Net-(U3A-OUT1)") (class "Default")
      (node (ref "C20") (pin "2") (pinfunction "2_2") (pintype "passive"))
      (node (ref "R7") (pin "1") (pinfunction "1_1") (pintype "passive"))
      (node (ref "U3") (pin "39") (pinfunction "OUT1_39") (pintype "tri_state"))
    )
    (net (code "47") (name "Net-(U3A-OUT4)") (class "Default")
      (node (ref "C24") (pin "2") (pinfunction "2_2") (pintype "passive"))
      (node (ref "R9") (pin "1") (pinfunction "1_1") (pintype "passive"))
      (node (ref "U3") (pin "19") (pinfunction "OUT4_19") (pintype "tri_state"))
    )
    (net (code "48") (name "Net-(U3A-REFIN_(REF1))") (class "Default")
      (node (ref "C25") (pin "1") (pinfunction "1_1") (pintype "passive"))
      (node (ref "U3") (pin "48") (pinfunction "REFIN_(REF1)_48") (pintype "input"))
    )
    (net (code "49") (name "Net-(U3A-RSET)") (class "Default")
      (node (ref "R11") (pin "2") (pinfunction "2_2") (pintype "passive"))
      (node (ref "U3") (pin "44") (pinfunction "RSET_44") (pintype "input"))
    )
    (net (code "50") (name "Net-(U3A-~{OUT0})") (class "Default")
      (node (ref "C19") (pin "2") (pinfunction "2_2") (pintype "passive"))
      (node (ref "R6") (pin "1") (pinfunction "1_1") (pintype "passive"))
      (node (ref "U3") (pin "41") (pinfunction "~{OUT0}_41") (pintype "tri_state"))
    )
    (net (code "51") (name "Net-(U3A-~{OUT1})") (class "Default")
      (node (ref "C22") (pin "2") (pinfunction "2_2") (pintype "passive"))
      (node (ref "R8") (pin "1") (pinfunction "1_1") (pintype "passive"))
      (node (ref "U3") (pin "38") (pinfunction "~{OUT1}_38") (pintype "tri_state"))
    )
    (net (code "52") (name "Net-(U3A-~{OUT4})") (class "Default")
      (node (ref "C27") (pin "2") (pinfunction "2_2") (pintype "passive"))
      (node (ref "R10") (pin "1") (pinfunction "1_1") (pintype "passive"))
      (node (ref "U3") (pin "20") (pinfunction "~{OUT4}_20") (pintype "tri_state"))
    )
    (net (code "53") (name "Net-(U3A-~{REFIN}_(REF2))") (class "Default")
      (node (ref "C26") (pin "1") (pinfunction "1_1") (pintype "passive"))
      (node (ref "U3") (pin "47") (pinfunction "~{REFIN}_(REF2)_47") (pintype "input"))
    )
    (net (code "54") (name "Net-(X1-OUT)") (class "Default")
      (node (ref "C25") (pin "2") (pinfunction "2_2") (pintype "passive"))
      (node (ref "X1") (pin "3") (pinfunction "OUT_3") (pintype "output"))
    )
    (net (code "55") (name "unconnected-(U2D-4Y-Pad11)") (class "Default")
      (node (ref "U2") (pin "11") (pinfunction "4Y_11") (pintype "output"))
    )
    (net (code "56") (name "unconnected-(U3A-NC-Pad36)") (class "Default")
      (node (ref "U3") (pin "36") (pinfunction "NC_36") (pintype "passive"))
    )
    (net (code "57") (name "unconnected-(U3A-OUT2-Pad33)") (class "Default")
      (node (ref "U3") (pin "33") (pinfunction "OUT2_33") (pintype "tri_state"))
    )
    (net (code "58") (name "unconnected-(U3A-OUT3-Pad29)") (class "Default")
      (node (ref "U3") (pin "29") (pinfunction "OUT3_29") (pintype "tri_state"))
    )
    (net (code "59") (name "unconnected-(U3A-OUT5-Pad22)") (class "Default")
      (node (ref "U3") (pin "22") (pinfunction "OUT5_22") (pintype "tri_state"))
    )
    (net (code "60") (name "unconnected-(U3A-REF_SEL-Pad6)") (class "Default")
      (node (ref "U3") (pin "6") (pinfunction "REF_SEL_6") (pintype "input+no_connect"))
    )
    (net (code "61") (name "unconnected-(U3A-~{OUT2}-Pad32)") (class "Default")
      (node (ref "U3") (pin "32") (pinfunction "~{OUT2}_32") (pintype "tri_state"))
    )
    (net (code "62") (name "unconnected-(U3A-~{OUT3}-Pad28)") (class "Default")
      (node (ref "U3") (pin "28") (pinfunction "~{OUT3}_28") (pintype "tri_state"))
    )
    (net (code "63") (name "unconnected-(U3A-~{OUT5}-Pad23)") (class "Default")
      (node (ref "U3") (pin "23") (pinfunction "~{OUT5}_23") (pintype "tri_state"))
    )
    (net (code "64") (name "unconnected-(U4D-4Y-Pad11)") (class "Default")
      (node (ref "U4") (pin "11") (pinfunction "4Y_11") (pintype "output"))
    )
  )
)
